# Mech_Interface_Zenith.net
KiCad netlist of a schematic drawn in Altium Designer
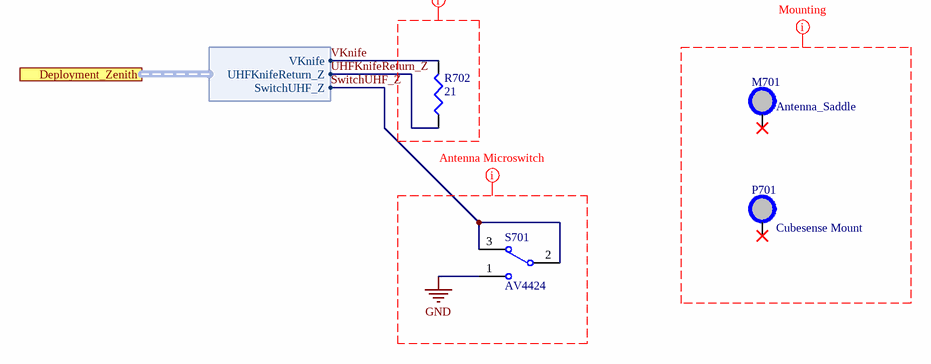
[diagram p0: Mech_Interface_Zenith.SchDoc]

(export (version "E")
  (design (tool "Eeschema 10.0.6"))
  (components
    (comp (ref "M701")
      (value "Antenna_Saddle")
      (footprint "ANTENNA_SADDLE")
      (fields
        (field (name "PART NUMBER") "PXX-ABS-00001")
        (field (name "MANUFACTURER PART NUMBER") "Custom")
        (field (name "PUBLISHER") "AlbertaSat")
      )
      (libsource (lib "Database") (part "Mounting_Hole"))
    )
    (comp (ref "P701")
      (value "Cubesense Mount")
      (footprint "Cubesense_Mount")
      (fields
        (field (name "PART NUMBER") "PXX-ABS-00006")
        (field (name "MANUFACTURER PART NUMBER") "Custom")
        (field (name "PUBLISHER") "AlbertaSat")
      )
      (libsource (lib "Database") (part "Mounting_Hole"))
    )
    (comp (ref "R702")
      (value "21")
      (footprint "VSH-CPF1")
      (description "21 Ohms ±1% 1W Through Hole Resistor Axial Flame Proof, Moisture Resistant, Safety Metal Film")
      (fields
        (field (name "PART NUMBER") "PR-VSH-00317")
        (field (name "MANUFACTURER PART NUMBER") "CPF121R000FKEE6")
        (field (name "PUBLISHER") "AlbertaSat")
      )
      (libsource (lib "Database") (part "Res3"))
    )
    (comp (ref "S701")
      (value "AV4424")
      (footprint "PANA-AV4424")
      (description "SWITCH SNAP ACT SPDT 500MA 30V")
      (fields (field (name "PART NUMBER") "20035"))
      (libsource (lib "Database") (part "SW-SPDT"))
    )
  )
  (nets
    (net (code "2") (name "/SwitchUHF_Z") (class "Default")
      (node (ref "S701") (pin "2") (pinfunction "COM_2") (pintype "passive"))
      (node (ref "S701") (pin "3") (pinfunction "NC_3") (pintype "passive"))
    )
    (net (code "3") (name "/UHFKnifeReturn_Z") (class "Default")
      (node (ref "R702") (pin "1") (pinfunction "1_1") (pintype "passive"))
    )
    (net (code "4") (name "/VKnife") (class "Default")
      (node (ref "R702") (pin "2") (pinfunction "2_2") (pintype "passive"))
    )
    (net (code "6") (name "GND") (class "Default")
      (node (ref "S701") (pin "1") (pinfunction "NO_1") (pintype "passive"))
    )
    (net (code "7") (name "unconnected-(M701-0-Pad1)") (class "Default")
      (node (ref "M701") (pin "1") (pinfunction "0_1") (pintype "passive+no_connect"))
    )
    (net (code "8") (name "unconnected-(P701-0-Pad1)") (class "Default")
      (node (ref "P701") (pin "1") (pinfunction "0_1") (pintype "passive+no_connect"))
    )
  )
)
